# client_board.net
KiCad netlist of a schematic drawn in EAGLE
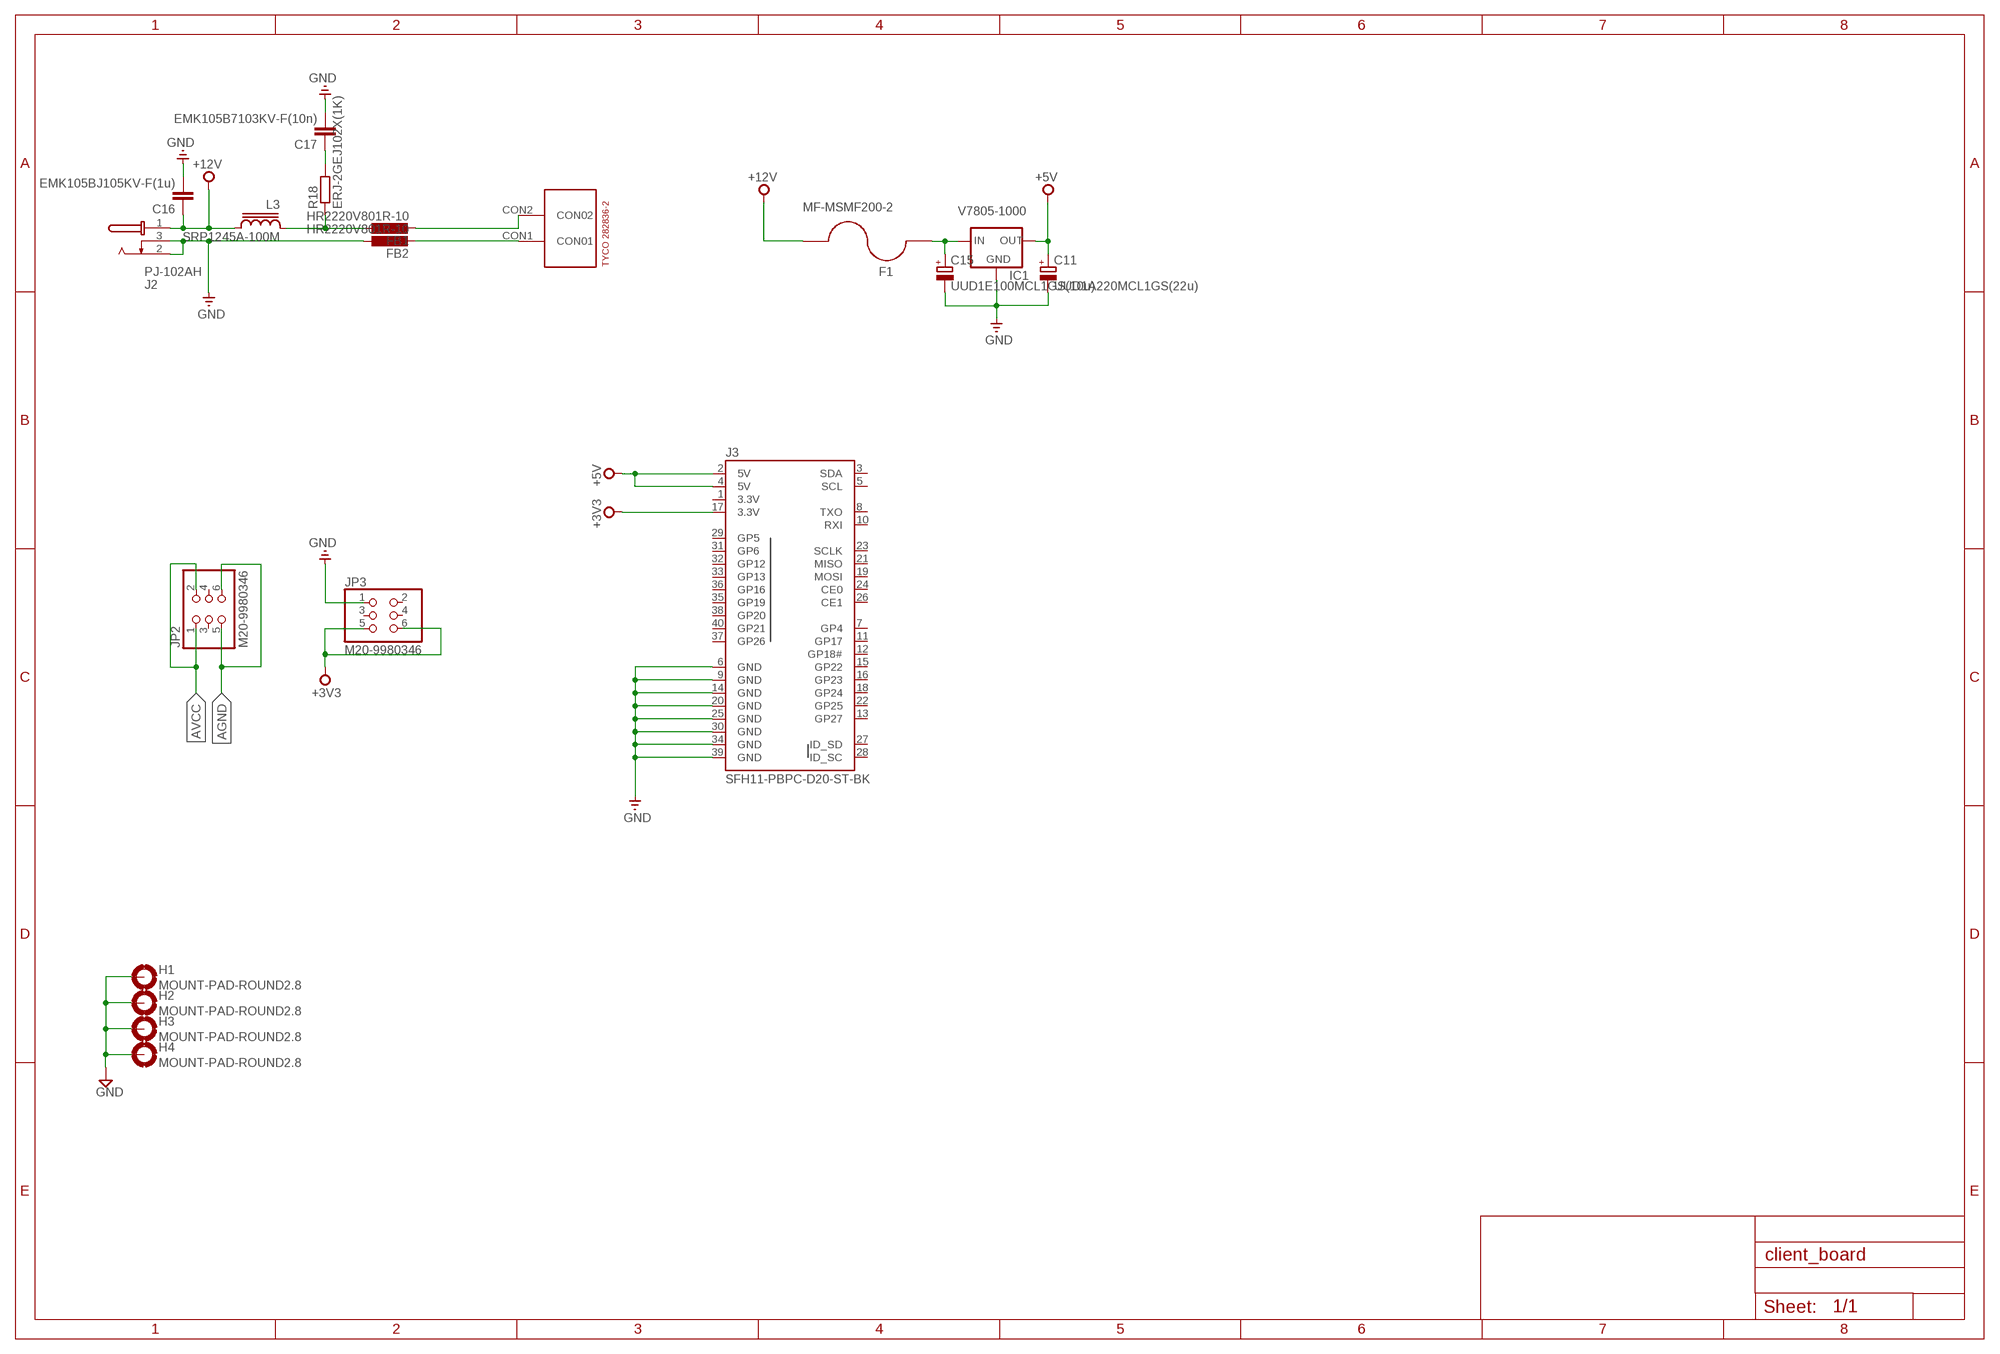
[diagram p0: schematic, sheet 1]

(export (version "E")
  (design (tool "Eeschema 10.0.6"))
  (components
    (comp (ref "C11")
      (value "UUD1A220MCL1GS(22u)")
      (footprint "eagle-import:153CLV-0405")
      (libsource (lib "eagle-import") (part "CPOL-EU153CLV-0405"))
    )
    (comp (ref "C15")
      (value "UUD1E100MCL1GS(10u)")
      (footprint "eagle-import:153CLV-0405")
      (libsource (lib "eagle-import") (part "CPOL-EU153CLV-0405"))
    )
    (comp (ref "C16")
      (value "EMK105BJ105KV-F(1u)")
      (footprint "eagle-import:C0402")
      (libsource (lib "eagle-import") (part "C-EUC0402"))
    )
    (comp (ref "C17")
      (value "EMK105B7103KV-F(10n)")
      (footprint "eagle-import:C0402")
      (libsource (lib "eagle-import") (part "C-EUC0402"))
    )
    (comp (ref "F1")
      (value "MF-MSMF200-2")
      (footprint "eagle-import:1812")
      (fields (field (name "MANUFACTURER") "Bourns Inc.") (field (name "PART_NUMBER") "MF-MSMF075/24-2"))
      (libsource (lib "eagle-import") (part "MF-MSMF?075/24"))
    )
    (comp (ref "FB1")
      (value "HR2220V801R-10")
      (footprint "eagle-import:L5650M")
      (libsource (lib "eagle-import") (part "L-EUL5650M"))
    )
    (comp (ref "FB2")
      (value "HR2220V801R-10")
      (footprint "eagle-import:L5650M")
      (libsource (lib "eagle-import") (part "L-EUL5650M"))
    )
    (comp (ref "H1")
      (value "MOUNT-PAD-ROUND2.8")
      (footprint "eagle-import:2,8-PAD")
      (libsource (lib "eagle-import") (part "MOUNT-PAD-ROUND2.8"))
    )
    (comp (ref "H2")
      (value "MOUNT-PAD-ROUND2.8")
      (footprint "eagle-import:2,8-PAD")
      (libsource (lib "eagle-import") (part "MOUNT-PAD-ROUND2.8"))
    )
    (comp (ref "H3")
      (value "MOUNT-PAD-ROUND2.8")
      (footprint "eagle-import:2,8-PAD")
      (libsource (lib "eagle-import") (part "MOUNT-PAD-ROUND2.8"))
    )
    (comp (ref "H4")
      (value "MOUNT-PAD-ROUND2.8")
      (footprint "eagle-import:2,8-PAD")
      (libsource (lib "eagle-import") (part "MOUNT-PAD-ROUND2.8"))
    )
    (comp (ref "IC1")
      (value "V7805-1000")
      (footprint "eagle-import:DIP_3PIN")
      (libsource (lib "eagle-import") (part "VR_1OUTXX"))
    )
    (comp (ref "J2")
      (value "PJ-102AH")
      (footprint "eagle-import:PJ-102XH")
      (libsource (lib "eagle-import") (part "PJ-102AH/BH"))
    )
    (comp (ref "J3")
      (value "SFH11-PBPC-D20-ST-BK")
      (footprint "eagle-import:2X20-SHROUDED")
      (libsource (lib "eagle-import") (part "RASPBERRYPI-40-PIN-GPIO"))
    )
    (comp (ref "JP2")
      (value "M20-9980346")
      (footprint "eagle-import:2X03")
      (libsource (lib "eagle-import") (part "PINHD-2X3"))
    )
    (comp (ref "JP3")
      (value "M20-9980346")
      (footprint "eagle-import:2X03")
      (libsource (lib "eagle-import") (part "PINHD-2X3"))
    )
    (comp (ref "L3")
      (value "SRP1245A-100M")
      (footprint "eagle-import:SRP1250A")
      (libsource (lib "eagle-import") (part "SRP1250A"))
    )
    (comp (ref "R18")
      (value "ERJ-2GEJ102X(1K)")
      (footprint "eagle-import:R0402")
      (libsource (lib "eagle-import") (part "R-EU_R0402"))
    )
    (comp (ref "U$1")
      (value "282836-2")
      (footprint "eagle-import:282836-2")
      (libsource (lib "eagle-import") (part "282836-2"))
    )
  )
  (nets
    (net (code "1") (name "+3V3") (class "Default")
      (node (ref "J3") (pin "17") (pinfunction "3.3V_17") (pintype "power_in"))
      (node (ref "JP3") (pin "5") (pinfunction "5_5") (pintype "passive"))
      (node (ref "JP3") (pin "6") (pinfunction "6_6") (pintype "passive"))
    )
    (net (code "2") (name "+5V") (class "Default")
      (node (ref "C11") (pin "+") (pinfunction "+_+") (pintype "passive"))
      (node (ref "IC1") (pin "OUT") (pinfunction "OUT_OUT") (pintype "passive"))
      (node (ref "J3") (pin "2") (pinfunction "5V_2") (pintype "power_in"))
      (node (ref "J3") (pin "4") (pinfunction "5V_4") (pintype "power_in"))
    )
    (net (code "3") (name "+12V") (class "Default")
      (node (ref "C16") (pin "1") (pinfunction "1_1") (pintype "passive"))
      (node (ref "F1") (pin "1") (pinfunction "1_1") (pintype "passive"))
      (node (ref "J2") (pin "1") (pinfunction "T_1") (pintype "passive"))
      (node (ref "L3") (pin "2") (pinfunction "2_2") (pintype "passive"))
    )
    (net (code "4") (name "/3.3V") (class "Default")
      (node (ref "J3") (pin "1") (pinfunction "3.3V_1") (pintype "power_in"))
    )
    (net (code "5") (name "AGND") (class "Default")
      (node (ref "FB2") (pin "2") (pinfunction "2_2") (pintype "passive"))
      (node (ref "JP2") (pin "5") (pinfunction "5_5") (pintype "passive"))
      (node (ref "JP2") (pin "6") (pinfunction "6_6") (pintype "passive"))
      (node (ref "U$1") (pin "CON1") (pinfunction "CON01_CON1") (pintype "bidirectional"))
    )
    (net (code "6") (name "AVCC") (class "Default")
      (node (ref "FB1") (pin "2") (pinfunction "2_2") (pintype "passive"))
      (node (ref "JP2") (pin "1") (pinfunction "1_1") (pintype "passive"))
      (node (ref "JP2") (pin "2") (pinfunction "2_2") (pintype "passive"))
      (node (ref "U$1") (pin "CON2") (pinfunction "CON02_CON2") (pintype "bidirectional"))
    )
    (net (code "7") (name "GND") (class "Default")
      (node (ref "C11") (pin "-") (pinfunction "-_-") (pintype "passive"))
      (node (ref "C15") (pin "-") (pinfunction "-_-") (pintype "passive"))
      (node (ref "C16") (pin "2") (pinfunction "2_2") (pintype "passive"))
      (node (ref "C17") (pin "2") (pinfunction "2_2") (pintype "passive"))
      (node (ref "FB2") (pin "1") (pinfunction "1_1") (pintype "passive"))
      (node (ref "H1") (pin "B2,8") (pinfunction "MOUNT_B2,8") (pintype "passive"))
      (node (ref "H2") (pin "B2,8") (pinfunction "MOUNT_B2,8") (pintype "passive"))
      (node (ref "H3") (pin "B2,8") (pinfunction "MOUNT_B2,8") (pintype "passive"))
      (node (ref "H4") (pin "B2,8") (pinfunction "MOUNT_B2,8") (pintype "passive"))
      (node (ref "IC1") (pin "GND") (pinfunction "GND_GND") (pintype "input"))
      (node (ref "J2") (pin "2") (pinfunction "S_2") (pintype "passive"))
      (node (ref "J2") (pin "3") (pinfunction "SS_3") (pintype "passive"))
      (node (ref "J3") (pin "14") (pinfunction "GND_14") (pintype "power_in"))
      (node (ref "J3") (pin "20") (pinfunction "GND_20") (pintype "power_in"))
      (node (ref "J3") (pin "25") (pinfunction "GND_25") (pintype "power_in"))
      (node (ref "J3") (pin "30") (pinfunction "GND_30") (pintype "power_in"))
      (node (ref "J3") (pin "34") (pinfunction "GND_34") (pintype "power_in"))
      (node (ref "J3") (pin "39") (pinfunction "GND_39") (pintype "power_in"))
      (node (ref "J3") (pin "6") (pinfunction "GND_6") (pintype "power_in"))
      (node (ref "J3") (pin "9") (pinfunction "GND_9") (pintype "power_in"))
      (node (ref "JP3") (pin "1") (pinfunction "1_1") (pintype "passive"))
    )
    (net (code "8") (name "Net-(C15-Pad+)") (class "Default")
      (node (ref "C15") (pin "+") (pinfunction "+_+") (pintype "passive"))
      (node (ref "F1") (pin "2") (pinfunction "2_2") (pintype "passive"))
      (node (ref "IC1") (pin "IN") (pinfunction "IN_IN") (pintype "input"))
    )
    (net (code "9") (name "Net-(C17-Pad1)") (class "Default")
      (node (ref "C17") (pin "1") (pinfunction "1_1") (pintype "passive"))
      (node (ref "R18") (pin "2") (pinfunction "2_2") (pintype "passive"))
    )
    (net (code "10") (name "Net-(FB1-Pad1)") (class "Default")
      (node (ref "FB1") (pin "1") (pinfunction "1_1") (pintype "passive"))
      (node (ref "L3") (pin "1") (pinfunction "1_1") (pintype "passive"))
      (node (ref "R18") (pin "1") (pinfunction "1_1") (pintype "passive"))
    )
    (net (code "11") (name "unconnected-(J3-CE0-Pad24)") (class "Default")
      (node (ref "J3") (pin "24") (pinfunction "CE0_24") (pintype "output"))
    )
    (net (code "12") (name "unconnected-(J3-CE1-Pad26)") (class "Default")
      (node (ref "J3") (pin "26") (pinfunction "CE1_26") (pintype "output"))
    )
    (net (code "13") (name "unconnected-(J3-GP4-Pad7)") (class "Default")
      (node (ref "J3") (pin "7") (pinfunction "GP4_7") (pintype "bidirectional"))
    )
    (net (code "14") (name "unconnected-(J3-GP5-Pad29)") (class "Default")
      (node (ref "J3") (pin "29") (pinfunction "GP5_29") (pintype "bidirectional"))
    )
    (net (code "15") (name "unconnected-(J3-GP6-Pad31)") (class "Default")
      (node (ref "J3") (pin "31") (pinfunction "GP6_31") (pintype "bidirectional"))
    )
    (net (code "16") (name "unconnected-(J3-GP12-Pad32)") (class "Default")
      (node (ref "J3") (pin "32") (pinfunction "GP12_32") (pintype "bidirectional"))
    )
    (net (code "17") (name "unconnected-(J3-GP13-Pad33)") (class "Default")
      (node (ref "J3") (pin "33") (pinfunction "GP13_33") (pintype "bidirectional"))
    )
    (net (code "18") (name "unconnected-(J3-GP16-Pad36)") (class "Default")
      (node (ref "J3") (pin "36") (pinfunction "GP16_36") (pintype "bidirectional"))
    )
    (net (code "19") (name "unconnected-(J3-GP17-Pad11)") (class "Default")
      (node (ref "J3") (pin "11") (pinfunction "GP17_11") (pintype "bidirectional"))
    )
    (net (code "20") (name "unconnected-(J3-GP18#-Pad12)") (class "Default")
      (node (ref "J3") (pin "12") (pinfunction "GP18#_12") (pintype "bidirectional"))
    )
    (net (code "21") (name "unconnected-(J3-GP19-Pad35)") (class "Default")
      (node (ref "J3") (pin "35") (pinfunction "GP19_35") (pintype "bidirectional"))
    )
    (net (code "22") (name "unconnected-(J3-GP20-Pad38)") (class "Default")
      (node (ref "J3") (pin "38") (pinfunction "GP20_38") (pintype "bidirectional"))
    )
    (net (code "23") (name "unconnected-(J3-GP21-Pad40)") (class "Default")
      (node (ref "J3") (pin "40") (pinfunction "GP21_40") (pintype "bidirectional"))
    )
    (net (code "24") (name "unconnected-(J3-GP22-Pad15)") (class "Default")
      (node (ref "J3") (pin "15") (pinfunction "GP22_15") (pintype "bidirectional"))
    )
    (net (code "25") (name "unconnected-(J3-GP23-Pad16)") (class "Default")
      (node (ref "J3") (pin "16") (pinfunction "GP23_16") (pintype "bidirectional"))
    )
    (net (code "26") (name "unconnected-(J3-GP24-Pad18)") (class "Default")
      (node (ref "J3") (pin "18") (pinfunction "GP24_18") (pintype "bidirectional"))
    )
    (net (code "27") (name "unconnected-(J3-GP25-Pad22)") (class "Default")
      (node (ref "J3") (pin "22") (pinfunction "GP25_22") (pintype "bidirectional"))
    )
    (net (code "28") (name "unconnected-(J3-GP26-Pad37)") (class "Default")
      (node (ref "J3") (pin "37") (pinfunction "GP26_37") (pintype "bidirectional"))
    )
    (net (code "29") (name "unconnected-(J3-GP27-Pad13)") (class "Default")
      (node (ref "J3") (pin "13") (pinfunction "GP27_13") (pintype "bidirectional"))
    )
    (net (code "30") (name "unconnected-(J3-ID_SC-Pad28)") (class "Default")
      (node (ref "J3") (pin "28") (pinfunction "ID_SC_28") (pintype "bidirectional"))
    )
    (net (code "31") (name "unconnected-(J3-ID_SD-Pad27)") (class "Default")
      (node (ref "J3") (pin "27") (pinfunction "ID_SD_27") (pintype "bidirectional"))
    )
    (net (code "32") (name "unconnected-(J3-MISO-Pad21)") (class "Default")
      (node (ref "J3") (pin "21") (pinfunction "MISO_21") (pintype "input"))
    )
    (net (code "33") (name "unconnected-(J3-MOSI-Pad19)") (class "Default")
      (node (ref "J3") (pin "19") (pinfunction "MOSI_19") (pintype "output"))
    )
    (net (code "34") (name "unconnected-(J3-RXI-Pad10)") (class "Default")
      (node (ref "J3") (pin "10") (pinfunction "RXI_10") (pintype "input"))
    )
    (net (code "35") (name "unconnected-(J3-SCL-Pad5)") (class "Default")
      (node (ref "J3") (pin "5") (pinfunction "SCL_5") (pintype "bidirectional"))
    )
    (net (code "36") (name "unconnected-(J3-SCLK-Pad23)") (class "Default")
      (node (ref "J3") (pin "23") (pinfunction "SCLK_23") (pintype "output"))
    )
    (net (code "37") (name "unconnected-(J3-SDA-Pad3)") (class "Default")
      (node (ref "J3") (pin "3") (pinfunction "SDA_3") (pintype "bidirectional"))
    )
    (net (code "38") (name "unconnected-(J3-TXO-Pad8)") (class "Default")
      (node (ref "J3") (pin "8") (pinfunction "TXO_8") (pintype "output"))
    )
    (net (code "39") (name "unconnected-(JP2-Pad3)") (class "Default")
      (node (ref "JP2") (pin "3") (pinfunction "3_3") (pintype "passive"))
    )
    (net (code "40") (name "unconnected-(JP2-Pad4)") (class "Default")
      (node (ref "JP2") (pin "4") (pinfunction "4_4") (pintype "passive"))
    )
    (net (code "41") (name "unconnected-(JP3-Pad2)") (class "Default")
      (node (ref "JP3") (pin "2") (pinfunction "2_2") (pintype "passive"))
    )
    (net (code "42") (name "unconnected-(JP3-Pad3)") (class "Default")
      (node (ref "JP3") (pin "3") (pinfunction "3_3") (pintype "passive"))
    )
    (net (code "43") (name "unconnected-(JP3-Pad4)") (class "Default")
      (node (ref "JP3") (pin "4") (pinfunction "4_4") (pintype "passive"))
    )
  )
)
